# ADC.net
KiCad netlist of a schematic drawn in Altium Designer
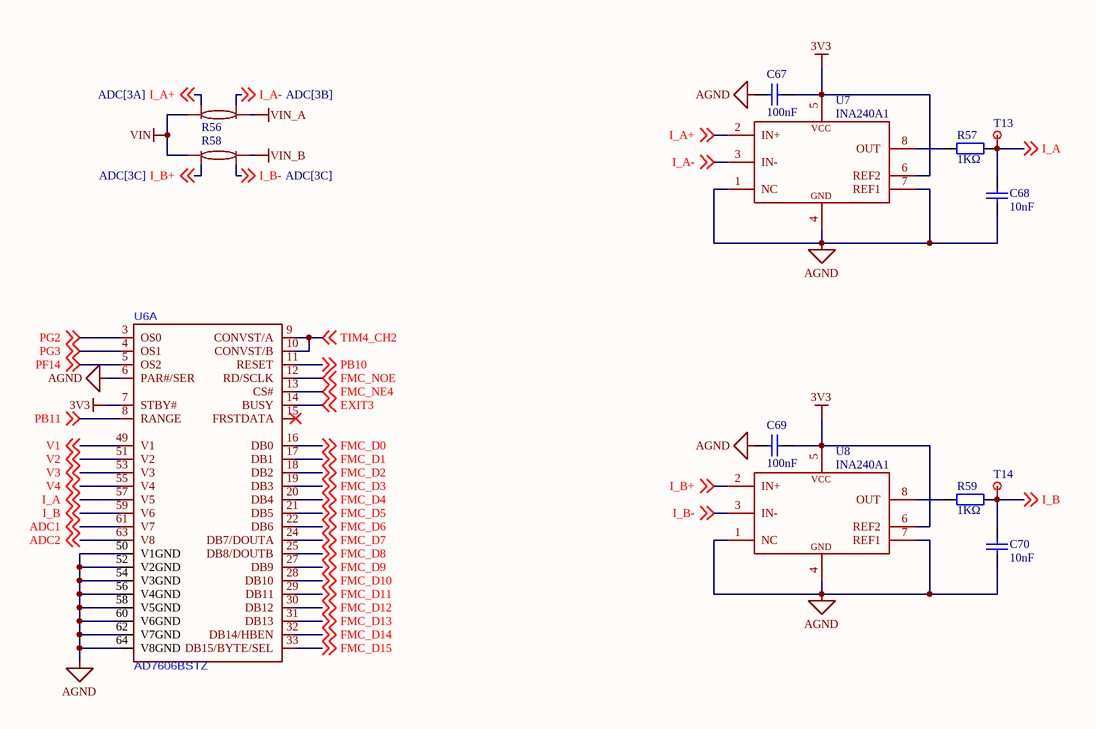
[diagram p0: ADC.SchDoc]

(export (version "E")
  (design (tool "Eeschema 10.0.6"))
  (components
    (comp (ref "C67")
      (value "100nF")
      (footprint "0402_C")
      (description "贴片电容")
      (libsource (lib "Miscellaneous Devices LC") (part "0402 100nF (104) 10% 16V"))
    )
    (comp (ref "C68")
      (value "10nF")
      (footprint "0402_C")
      (description "贴片电容")
      (libsource (lib "Miscellaneous Devices LC") (part "0402 100nF (104) 10% 16V"))
    )
    (comp (ref "C69")
      (value "100nF")
      (footprint "0402_C")
      (description "贴片电容")
      (libsource (lib "Miscellaneous Devices LC") (part "0402 100nF (104) 10% 16V"))
    )
    (comp (ref "C70")
      (value "10nF")
      (footprint "0402_C")
      (description "贴片电容")
      (libsource (lib "Miscellaneous Devices LC") (part "0402 100nF (104) 10% 16V"))
    )
    (comp (ref "R56")
      (value "1206_2mR_1W")
      (footprint "1206_2mΩ_1W")
      (libsource (lib "JiangCi") (part "1206_2mR_1W"))
    )
    (comp (ref "R57")
      (value "1KΩ")
      (footprint "0402_R")
      (description "贴片电阻")
      (libsource (lib "Miscellaneous Devices LC") (part "0402 0Ω (0R0) 1%"))
    )
    (comp (ref "R58")
      (value "1206_2mR_1W")
      (footprint "1206_2mΩ_1W")
      (libsource (lib "JiangCi") (part "1206_2mR_1W"))
    )
    (comp (ref "R59")
      (value "1KΩ")
      (footprint "0402_R")
      (description "贴片电阻")
      (libsource (lib "Miscellaneous Devices LC") (part "0402 0Ω (0R0) 1%"))
    )
    (comp (ref "T13")
      (value "testpoint")
      (footprint "testpoint")
      (libsource (lib "JiangCi") (part "testpoint"))
    )
    (comp (ref "T14")
      (value "testpoint")
      (footprint "testpoint")
      (libsource (lib "JiangCi") (part "testpoint"))
    )
    (comp (ref "U6")
      (value "AD7606BSTZ")
      (footprint "LQFP-64_L10.0-W10.0-P0.50-LS12.0-TL")
      (libsource (lib "JiangCi") (part "AD7606BSTZ"))
    )
    (comp (ref "U7")
      (value "INA240A1")
      (footprint "TSSOP8")
      (description "电流放大器")
      (libsource (lib "JiangCi") (part "INA240Ax"))
    )
    (comp (ref "U8")
      (value "INA240A1")
      (footprint "TSSOP8")
      (description "电流放大器")
      (libsource (lib "JiangCi") (part "INA240Ax"))
    )
  )
  (nets
    (net (code "1") (name "3V3") (class "Default")
      (node (ref "C67") (pin "1") (pinfunction "1_1") (pintype "passive"))
      (node (ref "C69") (pin "1") (pinfunction "1_1") (pintype "passive"))
      (node (ref "U6") (pin "7") (pinfunction "STBY#_7") (pintype "passive"))
      (node (ref "U7") (pin "5") (pinfunction "VS_5") (pintype "passive"))
      (node (ref "U7") (pin "6") (pinfunction "REF2_6") (pintype "passive"))
      (node (ref "U8") (pin "5") (pinfunction "VS_5") (pintype "passive"))
      (node (ref "U8") (pin "6") (pinfunction "REF2_6") (pintype "passive"))
    )
    (net (code "2") (name "ADC1") (class "Default")
      (node (ref "U6") (pin "61") (pinfunction "V7_61") (pintype "passive"))
    )
    (net (code "3") (name "ADC2") (class "Default")
      (node (ref "U6") (pin "63") (pinfunction "V8_63") (pintype "passive"))
    )
    (net (code "4") (name "AGND") (class "Default")
      (node (ref "C67") (pin "2") (pinfunction "2_2") (pintype "passive"))
      (node (ref "C68") (pin "2") (pinfunction "2_2") (pintype "passive"))
      (node (ref "C69") (pin "2") (pinfunction "2_2") (pintype "passive"))
      (node (ref "C70") (pin "2") (pinfunction "2_2") (pintype "passive"))
      (node (ref "U6") (pin "50") (pinfunction "V1GND_50") (pintype "passive"))
      (node (ref "U6") (pin "52") (pinfunction "V2GND_52") (pintype "passive"))
      (node (ref "U6") (pin "54") (pinfunction "V3GND_54") (pintype "passive"))
      (node (ref "U6") (pin "56") (pinfunction "V4GND_56") (pintype "passive"))
      (node (ref "U6") (pin "58") (pinfunction "V5GND_58") (pintype "passive"))
      (node (ref "U6") (pin "6") (pinfunction "PAR#/SER_6") (pintype "passive"))
      (node (ref "U6") (pin "60") (pinfunction "V6GND_60") (pintype "passive"))
      (node (ref "U6") (pin "62") (pinfunction "V7GND_62") (pintype "passive"))
      (node (ref "U6") (pin "64") (pinfunction "V8GND_64") (pintype "passive"))
      (node (ref "U7") (pin "1") (pinfunction "NC_1") (pintype "passive"))
      (node (ref "U7") (pin "4") (pinfunction "GND_4") (pintype "passive"))
      (node (ref "U7") (pin "7") (pinfunction "REF1_7") (pintype "passive"))
      (node (ref "U8") (pin "1") (pinfunction "NC_1") (pintype "passive"))
      (node (ref "U8") (pin "4") (pinfunction "GND_4") (pintype "passive"))
      (node (ref "U8") (pin "7") (pinfunction "REF1_7") (pintype "passive"))
    )
    (net (code "5") (name "EXIT3") (class "Default")
      (node (ref "U6") (pin "14") (pinfunction "BUSY_14") (pintype "passive"))
    )
    (net (code "6") (name "FMC_D0") (class "Default")
      (node (ref "U6") (pin "16") (pinfunction "DB0_16") (pintype "passive"))
    )
    (net (code "7") (name "FMC_D1") (class "Default")
      (node (ref "U6") (pin "17") (pinfunction "DB1_17") (pintype "passive"))
    )
    (net (code "8") (name "FMC_D2") (class "Default")
      (node (ref "U6") (pin "18") (pinfunction "DB2_18") (pintype "passive"))
    )
    (net (code "9") (name "FMC_D3") (class "Default")
      (node (ref "U6") (pin "19") (pinfunction "DB3_19") (pintype "passive"))
    )
    (net (code "10") (name "FMC_D4") (class "Default")
      (node (ref "U6") (pin "20") (pinfunction "DB4_20") (pintype "passive"))
    )
    (net (code "11") (name "FMC_D5") (class "Default")
      (node (ref "U6") (pin "21") (pinfunction "DB5_21") (pintype "passive"))
    )
    (net (code "12") (name "FMC_D6") (class "Default")
      (node (ref "U6") (pin "22") (pinfunction "DB6_22") (pintype "passive"))
    )
    (net (code "13") (name "FMC_D7") (class "Default")
      (node (ref "U6") (pin "24") (pinfunction "DB7/DOUTA_24") (pintype "passive"))
    )
    (net (code "14") (name "FMC_D8") (class "Default")
      (node (ref "U6") (pin "25") (pinfunction "DB8/DOUTB_25") (pintype "passive"))
    )
    (net (code "15") (name "FMC_D9") (class "Default")
      (node (ref "U6") (pin "27") (pinfunction "DB9_27") (pintype "passive"))
    )
    (net (code "16") (name "FMC_D10") (class "Default")
      (node (ref "U6") (pin "28") (pinfunction "DB10_28") (pintype "passive"))
    )
    (net (code "17") (name "FMC_D11") (class "Default")
      (node (ref "U6") (pin "29") (pinfunction "DB11_29") (pintype "passive"))
    )
    (net (code "18") (name "FMC_D12") (class "Default")
      (node (ref "U6") (pin "30") (pinfunction "DB12_30") (pintype "passive"))
    )
    (net (code "19") (name "FMC_D13") (class "Default")
      (node (ref "U6") (pin "31") (pinfunction "DB13_31") (pintype "passive"))
    )
    (net (code "20") (name "FMC_D14") (class "Default")
      (node (ref "U6") (pin "32") (pinfunction "DB14/HBEN_32") (pintype "passive"))
    )
    (net (code "21") (name "FMC_D15") (class "Default")
      (node (ref "U6") (pin "33") (pinfunction "DB15/BYTE/SEL_33") (pintype "passive"))
    )
    (net (code "22") (name "FMC_NE4") (class "Default")
      (node (ref "U6") (pin "13") (pinfunction "CS#_13") (pintype "passive"))
    )
    (net (code "23") (name "FMC_NOE") (class "Default")
      (node (ref "U6") (pin "12") (pinfunction "RD/SCLK_12") (pintype "passive"))
    )
    (net (code "24") (name "I_A") (class "Default")
      (node (ref "C68") (pin "1") (pinfunction "1_1") (pintype "passive"))
      (node (ref "R57") (pin "1") (pinfunction "1_1") (pintype "passive"))
      (node (ref "T13") (pin "1") (pinfunction "R_1") (pintype "passive"))
      (node (ref "U6") (pin "57") (pinfunction "V5_57") (pintype "passive"))
    )
    (net (code "25") (name "I_A+") (class "Default")
      (node (ref "R56") (pin "3") (pinfunction "3_3") (pintype "passive"))
      (node (ref "U7") (pin "2") (pinfunction "IN+_2") (pintype "passive"))
    )
    (net (code "26") (name "I_A-") (class "Default")
      (node (ref "R56") (pin "4") (pinfunction "4_4") (pintype "passive"))
      (node (ref "U7") (pin "3") (pinfunction "IN-_3") (pintype "passive"))
    )
    (net (code "27") (name "I_B") (class "Default")
      (node (ref "C70") (pin "1") (pinfunction "1_1") (pintype "passive"))
      (node (ref "R59") (pin "1") (pinfunction "1_1") (pintype "passive"))
      (node (ref "T14") (pin "1") (pinfunction "R_1") (pintype "passive"))
      (node (ref "U6") (pin "59") (pinfunction "V6_59") (pintype "passive"))
    )
    (net (code "28") (name "I_B+") (class "Default")
      (node (ref "R58") (pin "3") (pinfunction "3_3") (pintype "passive"))
      (node (ref "U8") (pin "2") (pinfunction "IN+_2") (pintype "passive"))
    )
    (net (code "29") (name "I_B-") (class "Default")
      (node (ref "R58") (pin "4") (pinfunction "4_4") (pintype "passive"))
      (node (ref "U8") (pin "3") (pinfunction "IN-_3") (pintype "passive"))
    )
    (net (code "30") (name "Net-(U7-OUT)") (class "Default")
      (node (ref "R57") (pin "2") (pinfunction "2_2") (pintype "passive"))
      (node (ref "U7") (pin "8") (pinfunction "OUT_8") (pintype "passive"))
    )
    (net (code "31") (name "Net-(U8-OUT)") (class "Default")
      (node (ref "R59") (pin "2") (pinfunction "2_2") (pintype "passive"))
      (node (ref "U8") (pin "8") (pinfunction "OUT_8") (pintype "passive"))
    )
    (net (code "32") (name "PB10") (class "Default")
      (node (ref "U6") (pin "11") (pinfunction "RESET_11") (pintype "passive"))
    )
    (net (code "33") (name "PB11") (class "Default")
      (node (ref "U6") (pin "8") (pinfunction "RANGE_8") (pintype "passive"))
    )
    (net (code "34") (name "PF14") (class "Default")
      (node (ref "U6") (pin "5") (pinfunction "OS2_5") (pintype "passive"))
    )
    (net (code "35") (name "PG2") (class "Default")
      (node (ref "U6") (pin "3") (pinfunction "OS0_3") (pintype "passive"))
    )
    (net (code "36") (name "PG3") (class "Default")
      (node (ref "U6") (pin "4") (pinfunction "OS1_4") (pintype "passive"))
    )
    (net (code "37") (name "TIM4_CH2") (class "Default")
      (node (ref "U6") (pin "10") (pinfunction "CONVST/B_10") (pintype "passive"))
      (node (ref "U6") (pin "9") (pinfunction "CONVST/A_9") (pintype "passive"))
    )
    (net (code "38") (name "V1") (class "Default")
      (node (ref "U6") (pin "49") (pinfunction "V1_49") (pintype "passive"))
    )
    (net (code "39") (name "V2") (class "Default")
      (node (ref "U6") (pin "51") (pinfunction "V2_51") (pintype "passive"))
    )
    (net (code "40") (name "V3") (class "Default")
      (node (ref "U6") (pin "53") (pinfunction "V3_53") (pintype "passive"))
    )
    (net (code "41") (name "V4") (class "Default")
      (node (ref "U6") (pin "55") (pinfunction "V4_55") (pintype "passive"))
    )
    (net (code "42") (name "VIN") (class "Default")
      (node (ref "R56") (pin "1") (pinfunction "1_1") (pintype "passive"))
      (node (ref "R58") (pin "1") (pinfunction "1_1") (pintype "passive"))
    )
    (net (code "43") (name "VIN_A") (class "Default")
      (node (ref "R56") (pin "2") (pinfunction "2_2") (pintype "passive"))
    )
    (net (code "44") (name "VIN_B") (class "Default")
      (node (ref "R58") (pin "2") (pinfunction "2_2") (pintype "passive"))
    )
    (net (code "45") (name "unconnected-(U6A-FRSTDATA-Pad15)") (class "Default")
      (node (ref "U6") (pin "15") (pinfunction "FRSTDATA_15") (pintype "passive+no_connect"))
    )
  )
)
